# ISOLATED_PS.net
KiCad netlist of a schematic drawn in Altium Designer
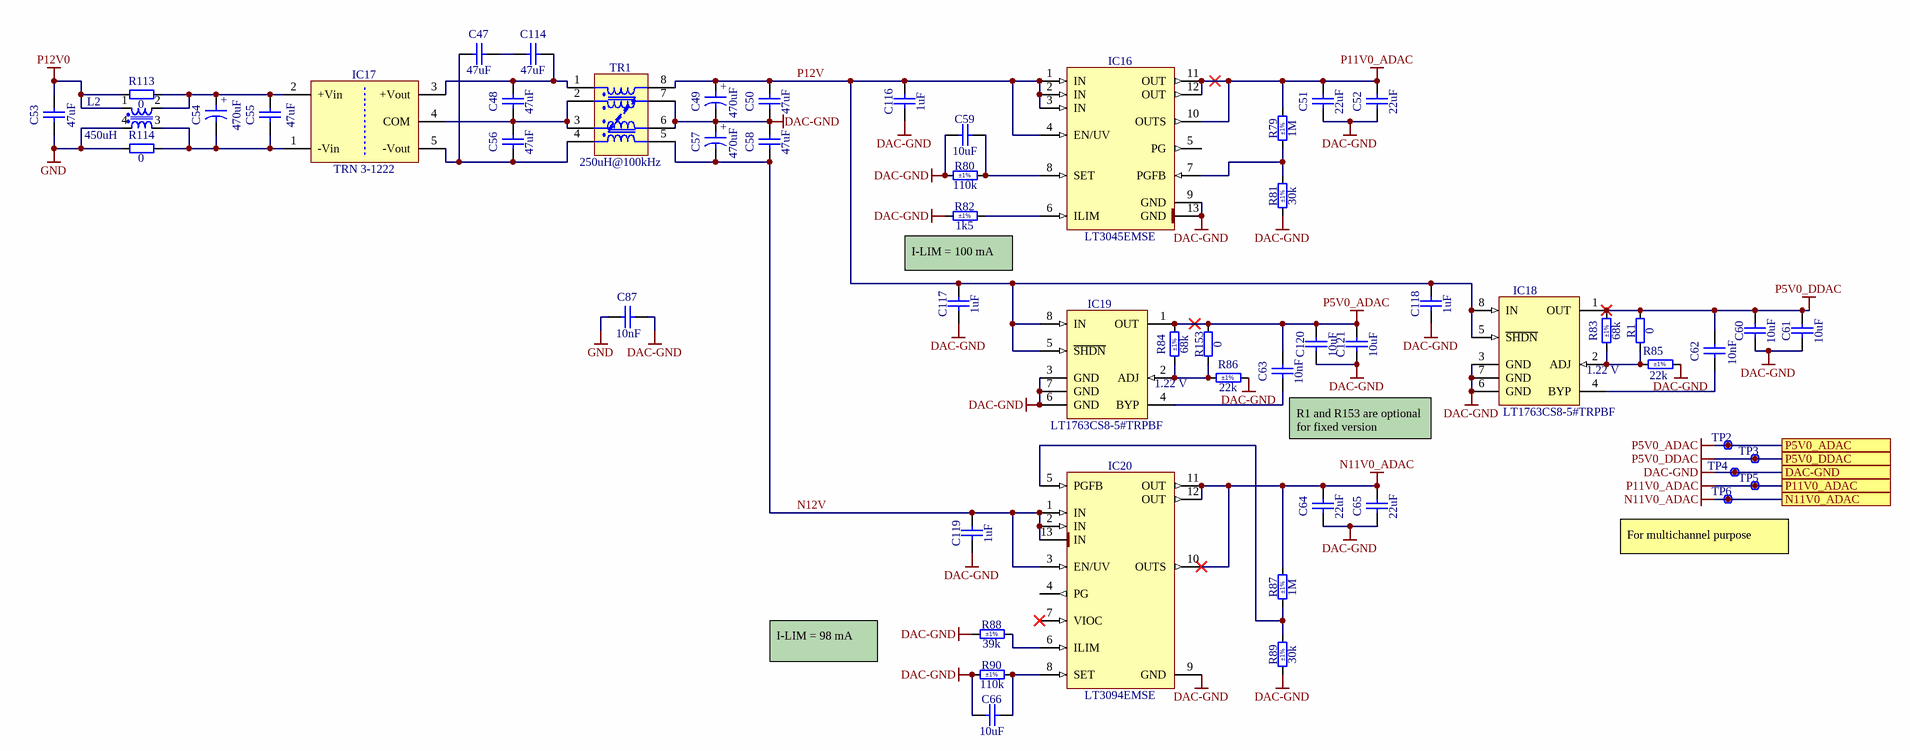
[diagram p0: ISOLATED_PS.SchDoc]

(export (version "E")
  (design (tool "Eeschema 10.0.6"))
  (components
    (comp (ref "C47")
      (value "47uF")
      (footprint "CAPC3225X270N")
      (description "Non-polarised capacitor")
      (fields
        (field (name "PART NUMBER") "CC1210_47UF_16V_20%_X5R")
        (field (name "VOLTAGE") "16V")
        (field (name "AUTHOR") "CERN DEM MR")
      )
      (libsource (lib "Capacitors") (part "Capacitor - non polarized"))
    )
    (comp (ref "C48")
      (value "47uF")
      (footprint "CAPC3225X270N")
      (description "Non-polarised capacitor")
      (fields
        (field (name "PART NUMBER") "CC1210_47UF_16V_20%_X5R")
        (field (name "VOLTAGE") "16V")
        (field (name "AUTHOR") "CERN DEM MR")
      )
      (libsource (lib "Capacitors") (part "Capacitor - non polarized"))
    )
    (comp (ref "C49")
      (value "470uF")
      (footprint "CAPAE1030X1020N")
      (description "Polarised capacitor")
      (fields
        (field (name "PART NUMBER") "CAE1030-1020_470UF_25V_20%")
        (field (name "VOLTAGE") "25V")
        (field (name "AUTHOR") "CERN DEM JLC")
      )
      (libsource (lib "Capacitors") (part "Capacitor - polarized"))
    )
    (comp (ref "C50")
      (value "47uF")
      (footprint "CAPC3225X270N")
      (description "Non-polarised capacitor")
      (fields
        (field (name "PART NUMBER") "CC1210_47UF_16V_20%_X5R")
        (field (name "VOLTAGE") "16V")
        (field (name "AUTHOR") "CERN DEM MR")
      )
      (libsource (lib "Capacitors") (part "Capacitor - non polarized"))
    )
    (comp (ref "C51")
      (value "22uF")
      (footprint "CAPC3216X180N")
      (description "Non-polarised capacitor")
      (fields
        (field (name "PART NUMBER") "CC1206_22UF_35V_20%_JB_TDK_C3216JB1V226M160AC")
        (field (name "VOLTAGE") "35V")
        (field (name "AUTHOR") "CERN DEM JLC")
      )
      (libsource (lib "Capacitors") (part "Capacitor - non polarized"))
    )
    (comp (ref "C52")
      (value "22uF")
      (footprint "CAPC3216X180N")
      (description "Non-polarised capacitor")
      (fields
        (field (name "PART NUMBER") "CC1206_22UF_35V_20%_JB_TDK_C3216JB1V226M160AC")
        (field (name "VOLTAGE") "35V")
        (field (name "AUTHOR") "CERN DEM JLC")
      )
      (libsource (lib "Capacitors") (part "Capacitor - non polarized"))
    )
    (comp (ref "C53")
      (value "47uF")
      (footprint "CAPC3225X270N")
      (description "Non-polarised capacitor")
      (fields
        (field (name "PART NUMBER") "CC1210_47UF_16V_20%_X5R")
        (field (name "VOLTAGE") "16V")
        (field (name "AUTHOR") "CERN DEM MR")
      )
      (libsource (lib "Capacitors") (part "Capacitor - non polarized"))
    )
    (comp (ref "C54")
      (value "470uF")
      (footprint "CAPAE1030X1020N")
      (description "Polarised capacitor")
      (fields
        (field (name "PART NUMBER") "CAE1030-1020_470UF_25V_20%")
        (field (name "VOLTAGE") "25V")
        (field (name "AUTHOR") "CERN DEM JLC")
      )
      (libsource (lib "Capacitors") (part "Capacitor - polarized"))
    )
    (comp (ref "C55")
      (value "47uF")
      (footprint "CAPC3225X270N")
      (description "Non-polarised capacitor")
      (fields
        (field (name "PART NUMBER") "CC1210_47UF_16V_20%_X5R")
        (field (name "VOLTAGE") "16V")
        (field (name "AUTHOR") "CERN DEM MR")
      )
      (libsource (lib "Capacitors") (part "Capacitor - non polarized"))
    )
    (comp (ref "C56")
      (value "47uF")
      (footprint "CAPC3225X270N")
      (description "Non-polarised capacitor")
      (fields
        (field (name "PART NUMBER") "CC1210_47UF_16V_20%_X5R")
        (field (name "VOLTAGE") "16V")
        (field (name "AUTHOR") "CERN DEM MR")
      )
      (libsource (lib "Capacitors") (part "Capacitor - non polarized"))
    )
    (comp (ref "C57")
      (value "470uF")
      (footprint "CAPAE1030X1020N")
      (description "Polarised capacitor")
      (fields
        (field (name "PART NUMBER") "CAE1030-1020_470UF_25V_20%")
        (field (name "VOLTAGE") "25V")
        (field (name "AUTHOR") "CERN DEM JLC")
      )
      (libsource (lib "Capacitors") (part "Capacitor - polarized"))
    )
    (comp (ref "C58")
      (value "47uF")
      (footprint "CAPC3225X270N")
      (description "Non-polarised capacitor")
      (fields
        (field (name "PART NUMBER") "CC1210_47UF_16V_20%_X5R")
        (field (name "VOLTAGE") "16V")
        (field (name "AUTHOR") "CERN DEM MR")
      )
      (libsource (lib "Capacitors") (part "Capacitor - non polarized"))
    )
    (comp (ref "C59")
      (value "10uF")
      (footprint "CAPC2012X135N")
      (description "Non-polarised capacitor")
      (fields
        (field (name "PART NUMBER") "CC0805_10UF_16V_10%_X5R")
        (field (name "VOLTAGE") "16V")
        (field (name "AUTHOR") "CERN DEM JLC")
      )
      (libsource (lib "Capacitors") (part "Capacitor - non polarized"))
    )
    (comp (ref "C60")
      (value "10uF")
      (footprint "CAPC2012X135N")
      (description "Non-polarised capacitor")
      (fields
        (field (name "PART NUMBER") "CC0805_10UF_16V_10%_X5R")
        (field (name "VOLTAGE") "16V")
        (field (name "AUTHOR") "CERN DEM JLC")
      )
      (libsource (lib "Capacitors") (part "Capacitor - non polarized"))
    )
    (comp (ref "C61")
      (value "10uF")
      (footprint "CAPC2012X135N")
      (description "Non-polarised capacitor")
      (fields
        (field (name "PART NUMBER") "CC0805_10UF_16V_10%_X5R")
        (field (name "VOLTAGE") "16V")
        (field (name "AUTHOR") "CERN DEM JLC")
      )
      (libsource (lib "Capacitors") (part "Capacitor - non polarized"))
    )
    (comp (ref "C62")
      (value "10nF")
      (footprint "CAPC1608X87N")
      (description "Non-polarised capacitor")
      (fields
        (field (name "PART NUMBER") "CC0603_10NF_50V_5%_C0G")
        (field (name "VOLTAGE") "50V")
        (field (name "AUTHOR") "CERN DEM JLC")
      )
      (libsource (lib "Capacitors") (part "Capacitor - non polarized"))
    )
    (comp (ref "C63")
      (value "10nF")
      (footprint "CAPC1608X87N")
      (description "Non-polarised capacitor")
      (fields
        (field (name "PART NUMBER") "CC0603_10NF_50V_5%_C0G")
        (field (name "VOLTAGE") "50V")
        (field (name "AUTHOR") "CERN DEM JLC")
      )
      (libsource (lib "Capacitors") (part "Capacitor - non polarized"))
    )
    (comp (ref "C64")
      (value "22uF")
      (footprint "CAPC3216X180N")
      (description "Non-polarised capacitor")
      (fields
        (field (name "PART NUMBER") "CC1206_22UF_35V_20%_JB_TDK_C3216JB1V226M160AC")
        (field (name "VOLTAGE") "35V")
        (field (name "AUTHOR") "CERN DEM JLC")
      )
      (libsource (lib "Capacitors") (part "Capacitor - non polarized"))
    )
    (comp (ref "C65")
      (value "22uF")
      (footprint "CAPC3216X180N")
      (description "Non-polarised capacitor")
      (fields
        (field (name "PART NUMBER") "CC1206_22UF_35V_20%_JB_TDK_C3216JB1V226M160AC")
        (field (name "VOLTAGE") "35V")
        (field (name "AUTHOR") "CERN DEM JLC")
      )
      (libsource (lib "Capacitors") (part "Capacitor - non polarized"))
    )
    (comp (ref "C66")
      (value "10uF")
      (footprint "CAPC2012X135N")
      (description "Non-polarised capacitor")
      (fields
        (field (name "PART NUMBER") "CC0805_10UF_16V_10%_X5R")
        (field (name "VOLTAGE") "16V")
        (field (name "AUTHOR") "CERN DEM JLC")
      )
      (libsource (lib "Capacitors") (part "Capacitor - non polarized"))
    )
    (comp (ref "C87")
      (value "10nF")
      (footprint "CAPC1608X87N")
      (description "Non-polarised capacitor")
      (fields
        (field (name "PART NUMBER") "CC0603_10NF_50V_5%_C0G")
        (field (name "VOLTAGE") "50V")
        (field (name "AUTHOR") "CERN DEM JLC")
      )
      (libsource (lib "Capacitors") (part "Capacitor - non polarized"))
    )
    (comp (ref "C114")
      (value "47uF")
      (footprint "CAPC3225X270N")
      (description "Non-polarised capacitor")
      (fields
        (field (name "PART NUMBER") "CC1210_47UF_16V_20%_X5R")
        (field (name "VOLTAGE") "16V")
        (field (name "AUTHOR") "CERN DEM MR")
      )
      (libsource (lib "Capacitors") (part "Capacitor - non polarized"))
    )
    (comp (ref "C116")
      (value "1uF")
      (footprint "CAPC1005X55N")
      (description "Non-polarised capacitor")
      (fields
        (field (name "PART NUMBER") "CC0402_1UF_16V_10%_X5R")
        (field (name "VOLTAGE") "16V")
        (field (name "AUTHOR") "CERN DEM JLC")
      )
      (libsource (lib "Capacitors") (part "Capacitor - non polarized"))
    )
    (comp (ref "C117")
      (value "1uF")
      (footprint "CAPC1005X55N")
      (description "Non-polarised capacitor")
      (fields
        (field (name "PART NUMBER") "CC0402_1UF_16V_10%_X5R")
        (field (name "VOLTAGE") "16V")
        (field (name "AUTHOR") "CERN DEM JLC")
      )
      (libsource (lib "Capacitors") (part "Capacitor - non polarized"))
    )
    (comp (ref "C118")
      (value "1uF")
      (footprint "CAPC1005X55N")
      (description "Non-polarised capacitor")
      (fields
        (field (name "PART NUMBER") "CC0402_1UF_16V_10%_X5R")
        (field (name "VOLTAGE") "16V")
        (field (name "AUTHOR") "CERN DEM JLC")
      )
      (libsource (lib "Capacitors") (part "Capacitor - non polarized"))
    )
    (comp (ref "C119")
      (value "1uF")
      (footprint "CAPC1005X55N")
      (description "Non-polarised capacitor")
      (fields
        (field (name "PART NUMBER") "CC0402_1UF_16V_10%_X5R")
        (field (name "VOLTAGE") "16V")
        (field (name "AUTHOR") "CERN DEM JLC")
      )
      (libsource (lib "Capacitors") (part "Capacitor - non polarized"))
    )
    (comp (ref "C120")
      (value "10uF")
      (footprint "CAPC2012X135N")
      (description "Non-polarised capacitor")
      (fields
        (field (name "PART NUMBER") "CC0805_10UF_16V_10%_X5R")
        (field (name "VOLTAGE") "16V")
        (field (name "AUTHOR") "CERN DEM JLC")
      )
      (libsource (lib "Capacitors") (part "Capacitor - non polarized"))
    )
    (comp (ref "C121")
      (value "10uF")
      (footprint "CAPC2012X135N")
      (description "Non-polarised capacitor")
      (fields
        (field (name "PART NUMBER") "CC0805_10UF_16V_10%_X5R")
        (field (name "VOLTAGE") "16V")
        (field (name "AUTHOR") "CERN DEM JLC")
      )
      (libsource (lib "Capacitors") (part "Capacitor - non polarized"))
    )
    (comp (ref "IC16")
      (value "LT3045EMSE")
      (footprint "SOP65P490X110-13N-R175X294")
      (description "20V, 500mA, Ultralow Noise, Ultrahigh PSRR Linear Regulator")
      (fields (field (name "MANUFACTURER") "LINEAR TECHNOLOGY") (field (name "AUTHOR") "CERN DEM HF"))
      (libsource (lib "ICs And Semiconductors") (part "LT3045"))
    )
    (comp (ref "IC17")
      (value "TRN 3-1222")
      (footprint "DCDC_TRACO_TRN3")
      (description "TRACO, TRN 3 Serie, Dual Output DCDC Converter")
      (fields (field (name "MANUFACTURER") "TRACO POWER") (field (name "AUTHOR") "CERN DEM JLC"))
      (libsource (lib "ICs And Semiconductors") (part "DCDC_TRACO_TRN3_Dual Output"))
    )
    (comp (ref "IC18")
      (value "LT1763CS8-5#TRPBF")
      (footprint "SOIC127P600X175-8N")
      (description "1.22V to 20V 500mA, Low Noise, LDO Adjustable Micropower Regulator")
      (fields
        (field (name "PART NUMBER") "LT1763CS8")
        (field (name "MANUFACTURER") "LINEAR TECHNOLOGY")
        (field (name "AUTHOR") "CERN DEM JLC")
      )
      (libsource (lib "ICs And Semiconductors") (part "LT1763xS8"))
    )
    (comp (ref "IC19")
      (value "LT1763CS8-5#TRPBF")
      (footprint "SOIC127P600X175-8N")
      (description "1.22V to 20V 500mA, Low Noise, LDO Adjustable Micropower Regulator")
      (fields
        (field (name "PART NUMBER") "LT1763CS8")
        (field (name "MANUFACTURER") "LINEAR TECHNOLOGY")
        (field (name "AUTHOR") "CERN DEM JLC")
      )
      (libsource (lib "ICs And Semiconductors") (part "LT1763xS8"))
    )
    (comp (ref "IC20")
      (value "LT3094EMSE")
      (footprint "SOP65P490X110-13N-R175X294")
      (description "-20V, 500mA, Ultralow Noise, Ultrahigh PSRR Negative Linear Regulator")
      (fields
        (field (name "PART NUMBER") "LT3094EMSE#PBF")
        (field (name "MANUFACTURER") "LINEAR TECHNOLOGY")
        (field (name "AUTHOR") "CERN DEM JLC")
      )
      (libsource (lib "ICs And Semiconductors") (part "LT3094"))
    )
    (comp (ref "L2")
      (value "450uH")
      (footprint "CMDC-9260-6500")
      (description "Inductor Common Mode")
      (fields
        (field (name "PART NUMBER") "IND_450UH_35%_TRACO_TCK-048")
        (field (name "POWER") "5.2A")
        (field (name "AUTHOR") "CERN DEM MR")
      )
      (libsource (lib "Inductors & Transformers") (part "Inductor Common Mode 1Dot-2 4Dot-3"))
    )
    (comp (ref "R1")
      (value "0")
      (footprint "RESC1608X55N")
      (description "Resistor")
      (fields
        (field (name "PART NUMBER") "R0603_0R_JUMPER")
        (field (name "MANUFACTURER") "GENERIC")
        (field (name "AUTHOR") "CERN DEM JLC")
      )
      (libsource (lib "Resistors") (part "Resistor"))
    )
    (comp (ref "R79")
      (value "1M")
      (footprint "RESC1005X40N")
      (description "Resistor - 1%")
      (fields
        (field (name "TOLERANCE") "±1%")
        (field (name "PART NUMBER") "R0402_1M_1%_0.0625W_100PPM")
        (field (name "POWER") "0.0625W")
        (field (name "AUTHOR") "CERN DEM JLC")
      )
      (libsource (lib "Resistors") (part "Resistor - 1%"))
    )
    (comp (ref "R80")
      (value "110k")
      (footprint "RESC1005X40N")
      (description "Resistor - 1%")
      (fields
        (field (name "TOLERANCE") "±1%")
        (field (name "PART NUMBER") "R0402_110K_1%_0.0625W_100PPM")
        (field (name "POWER") "0.0625W")
        (field (name "AUTHOR") "CERN DEM JLC")
      )
      (libsource (lib "Resistors") (part "Resistor - 1%"))
    )
    (comp (ref "R81")
      (value "30k")
      (footprint "RESC1005X40N")
      (description "Resistor - 1%")
      (fields
        (field (name "TOLERANCE") "±1%")
        (field (name "PART NUMBER") "R0402_30K_1%_0.0625W_100PPM")
        (field (name "POWER") "0.0625W")
        (field (name "AUTHOR") "CERN DEM JLC")
      )
      (libsource (lib "Resistors") (part "Resistor - 1%"))
    )
    (comp (ref "R82")
      (value "1k5")
      (footprint "RESC1005X40N")
      (description "Resistor - 1%")
      (fields
        (field (name "TOLERANCE") "±1%")
        (field (name "PART NUMBER") "R0402_1K5_1%_0.0625W_100PPM")
        (field (name "POWER") "0.0625W")
        (field (name "AUTHOR") "CERN DEM JLC")
      )
      (libsource (lib "Resistors") (part "Resistor - 1%"))
    )
    (comp (ref "R83")
      (value "68k")
      (footprint "RESC1608X55N")
      (description "Resistor - 1%")
      (fields
        (field (name "TOLERANCE") "±1%")
        (field (name "PART NUMBER") "R0603_68K_1%_0.1W_100PPM")
        (field (name "POWER") "0.1W")
        (field (name "AUTHOR") "CERN DEM JLC")
      )
      (libsource (lib "Resistors") (part "Resistor - 1%"))
    )
    (comp (ref "R84")
      (value "68k")
      (footprint "RESC1608X55N")
      (description "Resistor - 1%")
      (fields
        (field (name "TOLERANCE") "±1%")
        (field (name "PART NUMBER") "R0603_68K_1%_0.1W_100PPM")
        (field (name "POWER") "0.1W")
        (field (name "AUTHOR") "CERN DEM JLC")
      )
      (libsource (lib "Resistors") (part "Resistor - 1%"))
    )
    (comp (ref "R85")
      (value "22k")
      (footprint "RESC1608X55N")
      (description "Resistor - 1%")
      (fields
        (field (name "TOLERANCE") "±1%")
        (field (name "PART NUMBER") "R0603_22K_1%_0.1W_100PPM")
        (field (name "POWER") "0.1W")
        (field (name "AUTHOR") "CERN DEM JLC")
      )
      (libsource (lib "Resistors") (part "Resistor - 1%"))
    )
    (comp (ref "R86")
      (value "22k")
      (footprint "RESC1608X55N")
      (description "Resistor - 1%")
      (fields
        (field (name "TOLERANCE") "±1%")
        (field (name "PART NUMBER") "R0603_22K_1%_0.1W_100PPM")
        (field (name "POWER") "0.1W")
        (field (name "AUTHOR") "CERN DEM JLC")
      )
      (libsource (lib "Resistors") (part "Resistor - 1%"))
    )
    (comp (ref "R87")
      (value "1M")
      (footprint "RESC1005X40N")
      (description "Resistor - 1%")
      (fields
        (field (name "TOLERANCE") "±1%")
        (field (name "PART NUMBER") "R0402_1M_1%_0.0625W_100PPM")
        (field (name "POWER") "0.0625W")
        (field (name "AUTHOR") "CERN DEM JLC")
      )
      (libsource (lib "Resistors") (part "Resistor - 1%"))
    )
    (comp (ref "R88")
      (value "39k")
      (footprint "RESC1005X40N")
      (description "Resistor - 1%")
      (fields
        (field (name "TOLERANCE") "±1%")
        (field (name "PART NUMBER") "R0402_39K_1%_0.0625W_100PPM")
        (field (name "POWER") "0.0625W")
        (field (name "AUTHOR") "CERN DEM JLC")
      )
      (libsource (lib "Resistors") (part "Resistor - 1%"))
    )
    (comp (ref "R89")
      (value "30k")
      (footprint "RESC1005X40N")
      (description "Resistor - 1%")
      (fields
        (field (name "TOLERANCE") "±1%")
        (field (name "PART NUMBER") "R0402_30K_1%_0.0625W_100PPM")
        (field (name "POWER") "0.0625W")
        (field (name "AUTHOR") "CERN DEM JLC")
      )
      (libsource (lib "Resistors") (part "Resistor - 1%"))
    )
    (comp (ref "R90")
      (value "110k")
      (footprint "RESC1005X40N")
      (description "Resistor - 1%")
      (fields
        (field (name "TOLERANCE") "±1%")
        (field (name "PART NUMBER") "R0402_110K_1%_0.0625W_100PPM")
        (field (name "POWER") "0.0625W")
        (field (name "AUTHOR") "CERN DEM JLC")
      )
      (libsource (lib "Resistors") (part "Resistor - 1%"))
    )
    (comp (ref "R113")
      (value "0")
      (footprint "RESC2012X60N")
      (description "Resistor")
      (fields
        (field (name "PART NUMBER") "R0805_0R_JUMPER")
        (field (name "MANUFACTURER") "GENERIC")
        (field (name "AUTHOR") "CERN DEM JLC")
      )
      (libsource (lib "Resistors") (part "Resistor"))
    )
    (comp (ref "R114")
      (value "0")
      (footprint "RESC2012X60N")
      (description "Resistor")
      (fields
        (field (name "PART NUMBER") "R0805_0R_JUMPER")
        (field (name "MANUFACTURER") "GENERIC")
        (field (name "AUTHOR") "CERN DEM JLC")
      )
      (libsource (lib "Resistors") (part "Resistor"))
    )
    (comp (ref "R153")
      (value "0")
      (footprint "RESC1608X55N")
      (description "Resistor")
      (fields
        (field (name "PART NUMBER") "R0603_0R_JUMPER")
        (field (name "MANUFACTURER") "GENERIC")
        (field (name "AUTHOR") "CERN DEM JLC")
      )
      (libsource (lib "Resistors") (part "Resistor"))
    )
    (comp (ref "TP2")
      (value "Test Point")
      (footprint "TPS127")
      (fields (field (name "PART NUMBER") "SMD_PAD_1.27X1.27MM") (field (name "AUTHOR") "CERN DEM JLC"))
      (libsource (lib "Eletro-mechanical") (part "Test Point"))
    )
    (comp (ref "TP3")
      (value "Test Point")
      (footprint "TPS127")
      (fields (field (name "PART NUMBER") "SMD_PAD_1.27X1.27MM") (field (name "AUTHOR") "CERN DEM JLC"))
      (libsource (lib "Eletro-mechanical") (part "Test Point"))
    )
    (comp (ref "TP4")
      (value "Test Point")
      (footprint "VERO_20-313145")
      (fields
        (field (name "PART NUMBER") "VERO_20-313145")
        (field (name "MANUFACTURER") "VERO TECHNOLOGIES")
        (field (name "MANUFACTURER PART NUMBER") "20-313145")
        (field (name "AUTHOR") "CERN DEM JLC")
      )
      (libsource (lib "Connectors") (part "Test Point"))
    )
    (comp (ref "TP5")
      (value "Test Point")
      (footprint "TPS127")
      (fields (field (name "PART NUMBER") "SMD_PAD_1.27X1.27MM") (field (name "AUTHOR") "CERN DEM JLC"))
      (libsource (lib "Eletro-mechanical") (part "Test Point"))
    )
    (comp (ref "TP6")
      (value "Test Point")
      (footprint "TPS127")
      (fields (field (name "PART NUMBER") "SMD_PAD_1.27X1.27MM") (field (name "AUTHOR") "CERN DEM JLC"))
      (libsource (lib "Eletro-mechanical") (part "Test Point"))
    )
    (comp (ref "TR1")
      (value "250uH@100kHz")
      (footprint "IND_WURTH_WE-SL_74420")
      (description "Flyback Transformer")
      (fields
        (field (name "PART NUMBER") "IND_250UH_35%_WURTH_WE-SL_744204")
        (field (name "POWER") "600mA")
        (field (name "AUTHOR") "CERN DEM HF")
      )
      (libsource (lib "Inductors & Transformers") (part "IND_WURTH_WE-SL_74420 4 windings"))
    )
  )
  (nets
    (net (code "1") (name "/N12V") (class "Default")
      (node (ref "C119") (pin "2") (pinfunction "2_2") (pintype "passive"))
      (node (ref "C57") (pin "2") (pinfunction "2_2") (pintype "passive"))
      (node (ref "C58") (pin "1") (pinfunction "1_1") (pintype "passive"))
      (node (ref "IC20") (pin "1") (pinfunction "IN_1") (pintype "input"))
      (node (ref "IC20") (pin "13") (pinfunction "IN_13") (pintype "power_in"))
      (node (ref "IC20") (pin "2") (pinfunction "IN_2") (pintype "input"))
      (node (ref "IC20") (pin "3") (pinfunction "EN/UV_3") (pintype "input"))
      (node (ref "TR1") (pin "5") (pinfunction "5_5") (pintype "passive"))
    )
    (net (code "2") (name "/P12V") (class "Default")
      (node (ref "C116") (pin "2") (pinfunction "2_2") (pintype "passive"))
      (node (ref "C117") (pin "2") (pinfunction "2_2") (pintype "passive"))
      (node (ref "C118") (pin "2") (pinfunction "2_2") (pintype "passive"))
      (node (ref "C49") (pin "1") (pinfunction "1_1") (pintype "passive"))
      (node (ref "C50") (pin "2") (pinfunction "2_2") (pintype "passive"))
      (node (ref "IC16") (pin "1") (pinfunction "IN_1") (pintype "input"))
      (node (ref "IC16") (pin "2") (pinfunction "IN_2") (pintype "input"))
      (node (ref "IC16") (pin "3") (pinfunction "IN_3") (pintype "input"))
      (node (ref "IC16") (pin "4") (pinfunction "EN/UV_4") (pintype "input"))
      (node (ref "IC18") (pin "5") (pinfunction "~{SHDN}_5") (pintype "input"))
      (node (ref "IC18") (pin "8") (pinfunction "IN_8") (pintype "input"))
      (node (ref "IC19") (pin "5") (pinfunction "~{SHDN}_5") (pintype "input"))
      (node (ref "IC19") (pin "8") (pinfunction "IN_8") (pintype "input"))
      (node (ref "TR1") (pin "8") (pinfunction "8_8") (pintype "passive"))
    )
    (net (code "3") (name "DAC-GND") (class "Default")
      (node (ref "C116") (pin "1") (pinfunction "1_1") (pintype "passive"))
      (node (ref "C117") (pin "1") (pinfunction "1_1") (pintype "passive"))
      (node (ref "C118") (pin "1") (pinfunction "1_1") (pintype "passive"))
      (node (ref "C119") (pin "1") (pinfunction "1_1") (pintype "passive"))
      (node (ref "C120") (pin "1") (pinfunction "1_1") (pintype "passive"))
      (node (ref "C121") (pin "1") (pinfunction "1_1") (pintype "passive"))
      (node (ref "C49") (pin "2") (pinfunction "2_2") (pintype "passive"))
      (node (ref "C50") (pin "1") (pinfunction "1_1") (pintype "passive"))
      (node (ref "C51") (pin "1") (pinfunction "1_1") (pintype "passive"))
      (node (ref "C52") (pin "1") (pinfunction "1_1") (pintype "passive"))
      (node (ref "C57") (pin "1") (pinfunction "1_1") (pintype "passive"))
      (node (ref "C58") (pin "2") (pinfunction "2_2") (pintype "passive"))
      (node (ref "C59") (pin "1") (pinfunction "1_1") (pintype "passive"))
      (node (ref "C60") (pin "1") (pinfunction "1_1") (pintype "passive"))
      (node (ref "C61") (pin "1") (pinfunction "1_1") (pintype "passive"))
      (node (ref "C64") (pin "1") (pinfunction "1_1") (pintype "passive"))
      (node (ref "C65") (pin "1") (pinfunction "1_1") (pintype "passive"))
      (node (ref "C66") (pin "1") (pinfunction "1_1") (pintype "passive"))
      (node (ref "C87") (pin "2") (pinfunction "2_2") (pintype "passive"))
      (node (ref "IC16") (pin "13") (pinfunction "GND_13") (pintype "power_in"))
      (node (ref "IC16") (pin "9") (pinfunction "GND_9") (pintype "power_in"))
      (node (ref "IC18") (pin "3") (pinfunction "GND_3") (pintype "power_in"))
      (node (ref "IC18") (pin "6") (pinfunction "GND_6") (pintype "power_in"))
      (node (ref "IC18") (pin "7") (pinfunction "GND_7") (pintype "power_in"))
      (node (ref "IC19") (pin "3") (pinfunction "GND_3") (pintype "power_in"))
      (node (ref "IC19") (pin "6") (pinfunction "GND_6") (pintype "power_in"))
      (node (ref "IC19") (pin "7") (pinfunction "GND_7") (pintype "power_in"))
      (node (ref "IC20") (pin "9") (pinfunction "GND_9") (pintype "power_in"))
      (node (ref "R80") (pin "1") (pinfunction "1_1") (pintype "passive"))
      (node (ref "R81") (pin "1") (pinfunction "1_1") (pintype "passive"))
      (node (ref "R82") (pin "1") (pinfunction "1_1") (pintype "passive"))
      (node (ref "R85") (pin "1") (pinfunction "1_1") (pintype "passive"))
      (node (ref "R86") (pin "1") (pinfunction "1_1") (pintype "passive"))
      (node (ref "R88") (pin "1") (pinfunction "1_1") (pintype "passive"))
      (node (ref "R89") (pin "1") (pinfunction "1_1") (pintype "passive"))
      (node (ref "R90") (pin "1") (pinfunction "1_1") (pintype "passive"))
      (node (ref "TP4") (pin "1") (pinfunction "1_1") (pintype "bidirectional"))
      (node (ref "TR1") (pin "6") (pinfunction "6_6") (pintype "passive"))
      (node (ref "TR1") (pin "7") (pinfunction "7_7") (pintype "passive"))
    )
    (net (code "4") (name "GND") (class "Default")
      (node (ref "C53") (pin "2") (pinfunction "2_2") (pintype "passive"))
      (node (ref "C87") (pin "1") (pinfunction "1_1") (pintype "passive"))
      (node (ref "L2") (pin "4") (pinfunction "4_4") (pintype "passive"))
      (node (ref "R114") (pin "1") (pinfunction "1_1") (pintype "passive"))
    )
    (net (code "5") (name "N11V0_ADAC") (class "Default")
      (node (ref "C64") (pin "2") (pinfunction "2_2") (pintype "passive"))
      (node (ref "C65") (pin "2") (pinfunction "2_2") (pintype "passive"))
      (node (ref "IC20") (pin "10") (pinfunction "OUTS_10") (pintype "output"))
      (node (ref "IC20") (pin "11") (pinfunction "OUT_11") (pintype "output"))
      (node (ref "IC20") (pin "12") (pinfunction "OUT_12") (pintype "output"))
      (node (ref "R87") (pin "2") (pinfunction "2_2") (pintype "passive"))
      (node (ref "TP6") (pin "1") (pinfunction "1_1") (pintype "bidirectional"))
    )
    (net (code "6") (name "Net-(C114-Pad1)") (class "Default")
      (node (ref "C114") (pin "1") (pinfunction "1_1") (pintype "passive"))
      (node (ref "C47") (pin "2") (pinfunction "2_2") (pintype "passive"))
    )
    (net (code "7") (name "Net-(IC16-ILIM)") (class "Default")
      (node (ref "IC16") (pin "6") (pinfunction "ILIM_6") (pintype "input"))
      (node (ref "R82") (pin "2") (pinfunction "2_2") (pintype "passive"))
    )
    (net (code "8") (name "Net-(IC16-PGFB)") (class "Default")
      (node (ref "IC16") (pin "7") (pinfunction "PGFB_7") (pintype "input"))
      (node (ref "R79") (pin "1") (pinfunction "1_1") (pintype "passive"))
      (node (ref "R81") (pin "2") (pinfunction "2_2") (pintype "passive"))
    )
    (net (code "9") (name "Net-(IC16-SET)") (class "Default")
      (node (ref "C59") (pin "2") (pinfunction "2_2") (pintype "passive"))
      (node (ref "IC16") (pin "8") (pinfunction "SET_8") (pintype "input"))
      (node (ref "R80") (pin "2") (pinfunction "2_2") (pintype "passive"))
    )
    (net (code "10") (name "Net-(IC17-+Vin)") (class "Default")
      (node (ref "C54") (pin "1") (pinfunction "1_1") (pintype "passive"))
      (node (ref "C55") (pin "1") (pinfunction "1_1") (pintype "passive"))
      (node (ref "IC17") (pin "2") (pinfunction "+Vin_2") (pintype "power_in"))
      (node (ref "L2") (pin "2") (pinfunction "2_2") (pintype "passive"))
      (node (ref "R113") (pin "2") (pinfunction "2_2") (pintype "passive"))
    )
    (net (code "11") (name "Net-(IC17-+Vout)") (class "Default")
      (node (ref "C114") (pin "2") (pinfunction "2_2") (pintype "passive"))
      (node (ref "C48") (pin "2") (pinfunction "2_2") (pintype "passive"))
      (node (ref "IC17") (pin "3") (pinfunction "+Vout_3") (pintype "power_in"))
      (node (ref "TR1") (pin "1") (pinfunction "NC_1") (pintype "passive"))
    )
    (net (code "12") (name "Net-(IC17--Vin)") (class "Default")
      (node (ref "C54") (pin "2") (pinfunction "2_2") (pintype "passive"))
      (node (ref "C55") (pin "2") (pinfunction "2_2") (pintype "passive"))
      (node (ref "IC17") (pin "1") (pinfunction "-Vin_1") (pintype "power_in"))
      (node (ref "L2") (pin "3") (pinfunction "3_3") (pintype "passive"))
      (node (ref "R114") (pin "2") (pinfunction "2_2") (pintype "passive"))
    )
    (net (code "13") (name "Net-(IC17--Vout)") (class "Default")
      (node (ref "C47") (pin "1") (pinfunction "1_1") (pintype "passive"))
      (node (ref "C56") (pin "1") (pinfunction "1_1") (pintype "passive"))
      (node (ref "IC17") (pin "5") (pinfunction "-Vout_5") (pintype "power_in"))
      (node (ref "TR1") (pin "4") (pinfunction "4_4") (pintype "passive"))
    )
    (net (code "14") (name "Net-(IC17-COM)") (class "Default")
      (node (ref "C48") (pin "1") (pinfunction "1_1") (pintype "passive"))
      (node (ref "C56") (pin "2") (pinfunction "2_2") (pintype "passive"))
      (node (ref "IC17") (pin "4") (pinfunction "COM_4") (pintype "power_in"))
      (node (ref "TR1") (pin "2") (pinfunction "2_2") (pintype "passive"))
      (node (ref "TR1") (pin "3") (pinfunction "3_3") (pintype "passive"))
    )
    (net (code "15") (name "Net-(IC18-ADJ)") (class "Default")
      (node (ref "IC18") (pin "2") (pinfunction "ADJ_2") (pintype "input"))
      (node (ref "R1") (pin "1") (pinfunction "1_1") (pintype "passive"))
      (node (ref "R83") (pin "1") (pinfunction "1_1") (pintype "passive"))
      (node (ref "R85") (pin "2") (pinfunction "2_2") (pintype "passive"))
    )
    (net (code "16") (name "Net-(IC18-BYP)") (class "Default")
      (node (ref "C62") (pin "1") (pinfunction "1_1") (pintype "passive"))
      (node (ref "IC18") (pin "4") (pinfunction "BYP_4") (pintype "passive"))
    )
    (net (code "17") (name "Net-(IC19-ADJ)") (class "Default")
      (node (ref "IC19") (pin "2") (pinfunction "ADJ_2") (pintype "input"))
      (node (ref "R153") (pin "1") (pinfunction "1_1") (pintype "passive"))
      (node (ref "R84") (pin "1") (pinfunction "1_1") (pintype "passive"))
      (node (ref "R86") (pin "2") (pinfunction "2_2") (pintype "passive"))
    )
    (net (code "18") (name "Net-(IC19-BYP)") (class "Default")
      (node (ref "C63") (pin "1") (pinfunction "1_1") (pintype "passive"))
      (node (ref "IC19") (pin "4") (pinfunction "BYP_4") (pintype "passive"))
    )
    (net (code "19") (name "Net-(IC20-ILIM)") (class "Default")
      (node (ref "IC20") (pin "6") (pinfunction "ILIM_6") (pintype "input"))
      (node (ref "R88") (pin "2") (pinfunction "2_2") (pintype "passive"))
    )
    (net (code "20") (name "Net-(IC20-PGFB)") (class "Default")
      (node (ref "IC20") (pin "5") (pinfunction "PGFB_5") (pintype "input"))
      (node (ref "R87") (pin "1") (pinfunction "1_1") (pintype "passive"))
      (node (ref "R89") (pin "2") (pinfunction "2_2") (pintype "passive"))
    )
    (net (code "21") (name "Net-(IC20-SET)") (class "Default")
      (node (ref "C66") (pin "2") (pinfunction "2_2") (pintype "passive"))
      (node (ref "IC20") (pin "8") (pinfunction "SET_8") (pintype "input"))
      (node (ref "R90") (pin "2") (pinfunction "2_2") (pintype "passive"))
    )
    (net (code "22") (name "P5V0_ADAC") (class "Default")
      (node (ref "C120") (pin "2") (pinfunction "2_2") (pintype "passive"))
      (node (ref "C121") (pin "2") (pinfunction "2_2") (pintype "passive"))
      (node (ref "C63") (pin "2") (pinfunction "2_2") (pintype "passive"))
      (node (ref "IC19") (pin "1") (pinfunction "OUT_1") (pintype "power_in"))
      (node (ref "R153") (pin "2") (pinfunction "2_2") (pintype "passive"))
      (node (ref "R84") (pin "2") (pinfunction "2_2") (pintype "passive"))
      (node (ref "TP2") (pin "1") (pinfunction "1_1") (pintype "bidirectional"))
    )
    (net (code "23") (name "P5V0_DDAC") (class "Default")
      (node (ref "C60") (pin "2") (pinfunction "2_2") (pintype "passive"))
      (node (ref "C61") (pin "2") (pinfunction "2_2") (pintype "passive"))
      (node (ref "C62") (pin "2") (pinfunction "2_2") (pintype "passive"))
      (node (ref "IC18") (pin "1") (pinfunction "OUT_1") (pintype "power_in"))
      (node (ref "R1") (pin "2") (pinfunction "2_2") (pintype "passive"))
      (node (ref "R83") (pin "2") (pinfunction "2_2") (pintype "passive"))
      (node (ref "TP3") (pin "1") (pinfunction "1_1") (pintype "bidirectional"))
    )
    (net (code "24") (name "P11V0_ADAC") (class "Default")
      (node (ref "C51") (pin "2") (pinfunction "2_2") (pintype "passive"))
      (node (ref "C52") (pin "2") (pinfunction "2_2") (pintype "passive"))
      (node (ref "IC16") (pin "10") (pinfunction "OUTS_10") (pintype "output"))
      (node (ref "IC16") (pin "11") (pinfunction "OUT_11") (pintype "output"))
      (node (ref "IC16") (pin "12") (pinfunction "OUT_12") (pintype "output"))
      (node (ref "R79") (pin "2") (pinfunction "2_2") (pintype "passive"))
      (node (ref "TP5") (pin "1") (pinfunction "1_1") (pintype "bidirectional"))
    )
    (net (code "25") (name "P12V0") (class "Default")
      (node (ref "C53") (pin "1") (pinfunction "1_1") (pintype "passive"))
      (node (ref "L2") (pin "1") (pinfunction "1_1") (pintype "passive"))
      (node (ref "R113") (pin "1") (pinfunction "1_1") (pintype "passive"))
    )
    (net (code "26") (name "unconnected-(IC16-PG-Pad5)") (class "Default")
      (node (ref "IC16") (pin "5") (pinfunction "PG_5") (pintype "output"))
    )
    (net (code "27") (name "unconnected-(IC20-PG-Pad4)") (class "Default")
      (node (ref "IC20") (pin "4") (pinfunction "PG_4") (pintype "output"))
    )
    (net (code "28") (name "unconnected-(IC20-VIOC-Pad7)") (class "Default")
      (node (ref "IC20") (pin "7") (pinfunction "VIOC_7") (pintype "input+no_connect"))
    )
  )
)
